# RevB.net
KiCad netlist of a schematic drawn in EAGLE
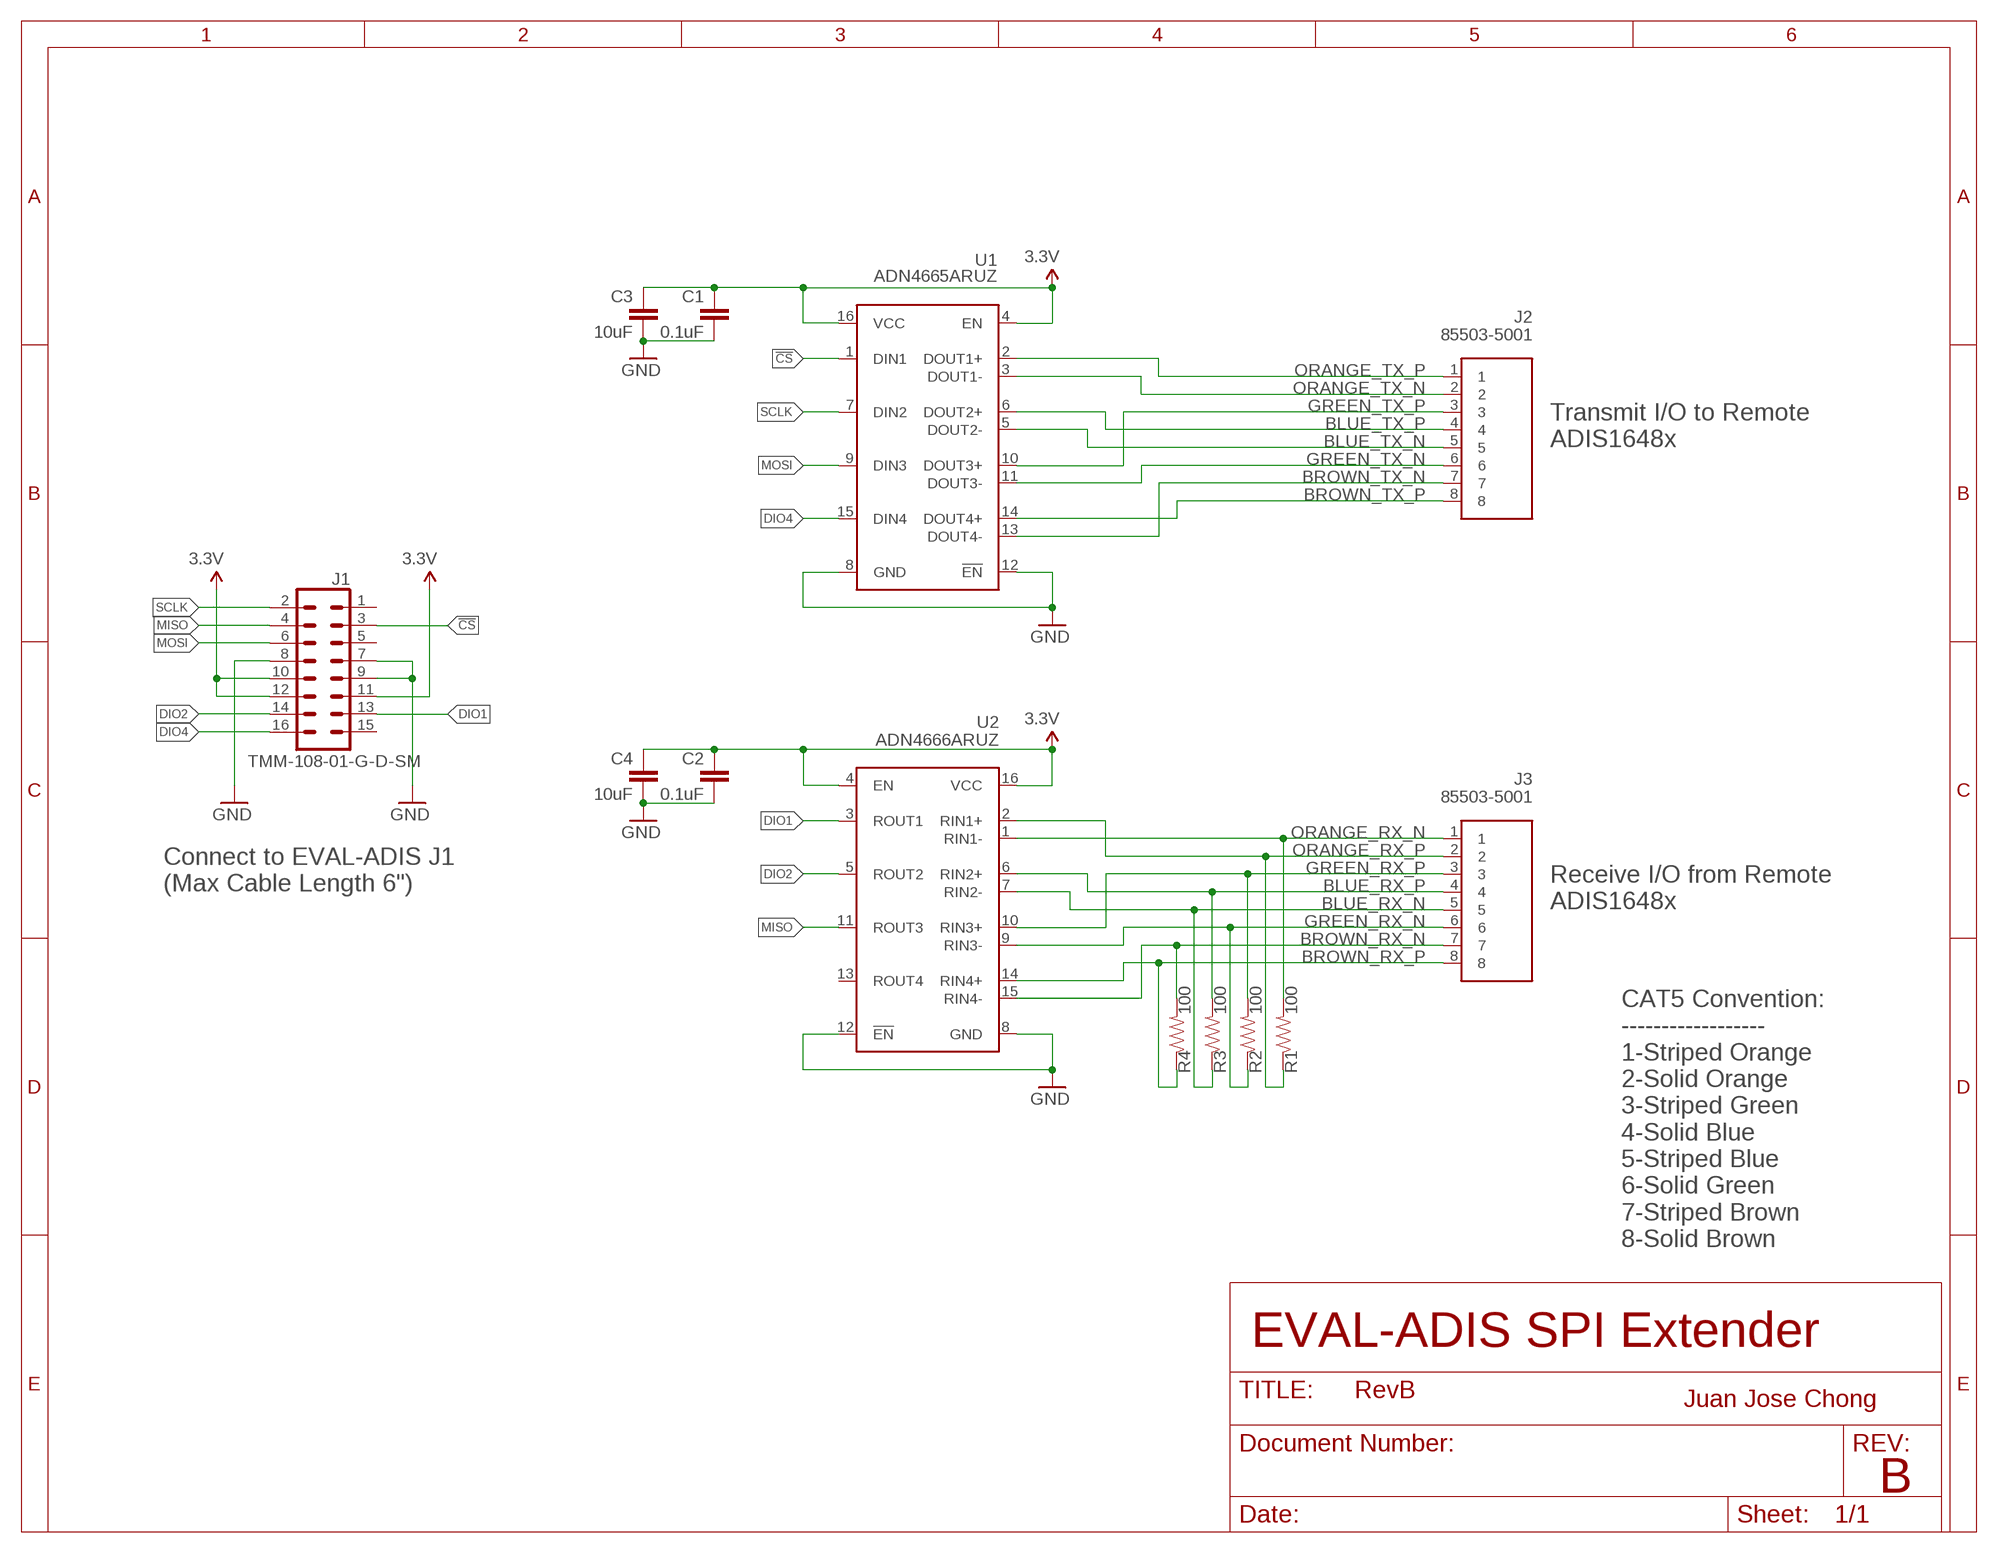
[diagram p0: schematic, sheet 1]

(export (version "E")
  (design (tool "Eeschema 10.0.6"))
  (components
    (comp (ref "C1")
      (value "0.1uF")
      (footprint "eagle-import:0805")
      (fields (field (name "PARTNO") "CL10B104KB8NNNC"))
      (libsource (lib "eagle-import") (part "CAP0805"))
    )
    (comp (ref "C2")
      (value "0.1uF")
      (footprint "eagle-import:0805")
      (fields (field (name "PARTNO") "CL10B104KB8NNNC"))
      (libsource (lib "eagle-import") (part "CAP0805"))
    )
    (comp (ref "C3")
      (value "10uF")
      (footprint "eagle-import:1206")
      (fields (field (name "PARTNO") "F931C106MAA"))
      (libsource (lib "eagle-import") (part "CAP1206"))
    )
    (comp (ref "C4")
      (value "10uF")
      (footprint "eagle-import:1206")
      (fields (field (name "PARTNO") "F931C106MAA"))
      (libsource (lib "eagle-import") (part "CAP1206"))
    )
    (comp (ref "J1")
      (value "TMM-108-01-G-D-SM")
      (footprint "eagle-import:TMM-108-XX-X-D")
      (libsource (lib "eagle-import") (part "TMM-108-XX-X-D"))
    )
    (comp (ref "J2")
      (value "85503-5001")
      (footprint "eagle-import:85503-5001")
      (fields (field (name "PARTNO") "855035001"))
      (libsource (lib "eagle-import") (part "85503-5001"))
    )
    (comp (ref "J3")
      (value "85503-5001")
      (footprint "eagle-import:85503-5001")
      (fields (field (name "PARTNO") "855035001"))
      (libsource (lib "eagle-import") (part "85503-5001"))
    )
    (comp (ref "R1")
      (value "100")
      (footprint "eagle-import:0603-RES")
      (fields (field (name "PARTNO") "ERJ-3EKF1000V"))
      (libsource (lib "eagle-import") (part "RESISTOR0603-RES"))
    )
    (comp (ref "R2")
      (value "100")
      (footprint "eagle-import:0603-RES")
      (fields (field (name "PARTNO") "ERJ-3EKF1000V"))
      (libsource (lib "eagle-import") (part "RESISTOR0603-RES"))
    )
    (comp (ref "R3")
      (value "100")
      (footprint "eagle-import:0603-RES")
      (fields (field (name "PARTNO") "ERJ-3EKF1000V"))
      (libsource (lib "eagle-import") (part "RESISTOR0603-RES"))
    )
    (comp (ref "R4")
      (value "100")
      (footprint "eagle-import:0603-RES")
      (fields (field (name "PARTNO") "ERJ-3EKF1000V"))
      (libsource (lib "eagle-import") (part "RESISTOR0603-RES"))
    )
    (comp (ref "U1")
      (value "ADN4665ARUZ")
      (footprint "eagle-import:TSSOP-16")
      (libsource (lib "eagle-import") (part "ADN4665ARUZ"))
    )
    (comp (ref "U2")
      (value "ADN4666ARUZ")
      (footprint "eagle-import:TSSOP-16")
      (libsource (lib "eagle-import") (part "ADN4666ARUZ"))
    )
  )
  (nets
    (net (code "1") (name "/BLUE_RX_N") (class "Default")
      (node (ref "J3") (pin "5") (pinfunction "5_5") (pintype "bidirectional"))
      (node (ref "R3") (pin "1") (pinfunction "1_1") (pintype "passive"))
      (node (ref "U2") (pin "7") (pinfunction "RIN2-_7") (pintype "bidirectional"))
    )
    (net (code "2") (name "/BLUE_RX_P") (class "Default")
      (node (ref "J3") (pin "4") (pinfunction "4_4") (pintype "bidirectional"))
      (node (ref "R3") (pin "2") (pinfunction "2_2") (pintype "passive"))
      (node (ref "U2") (pin "6") (pinfunction "RIN2+_6") (pintype "bidirectional"))
    )
    (net (code "3") (name "/BLUE_TX_N") (class "Default")
      (node (ref "J2") (pin "5") (pinfunction "5_5") (pintype "bidirectional"))
      (node (ref "U1") (pin "5") (pinfunction "DOUT2-_5") (pintype "bidirectional"))
    )
    (net (code "4") (name "/BLUE_TX_P") (class "Default")
      (node (ref "J2") (pin "4") (pinfunction "4_4") (pintype "bidirectional"))
      (node (ref "U1") (pin "6") (pinfunction "DOUT2+_6") (pintype "bidirectional"))
    )
    (net (code "5") (name "/BROWN_RX_N") (class "Default")
      (node (ref "J3") (pin "7") (pinfunction "7_7") (pintype "bidirectional"))
      (node (ref "R4") (pin "2") (pinfunction "2_2") (pintype "passive"))
      (node (ref "U2") (pin "15") (pinfunction "RIN4-_15") (pintype "bidirectional"))
    )
    (net (code "6") (name "/BROWN_RX_P") (class "Default")
      (node (ref "J3") (pin "8") (pinfunction "8_8") (pintype "bidirectional"))
      (node (ref "R4") (pin "1") (pinfunction "1_1") (pintype "passive"))
      (node (ref "U2") (pin "14") (pinfunction "RIN4+_14") (pintype "bidirectional"))
    )
    (net (code "7") (name "/BROWN_TX_N") (class "Default")
      (node (ref "J2") (pin "7") (pinfunction "7_7") (pintype "bidirectional"))
      (node (ref "U1") (pin "13") (pinfunction "DOUT4-_13") (pintype "bidirectional"))
    )
    (net (code "8") (name "/BROWN_TX_P") (class "Default")
      (node (ref "J2") (pin "8") (pinfunction "8_8") (pintype "bidirectional"))
      (node (ref "U1") (pin "14") (pinfunction "DOUT4+_14") (pintype "bidirectional"))
    )
    (net (code "9") (name "/GREEN_RX_N") (class "Default")
      (node (ref "J3") (pin "6") (pinfunction "6_6") (pintype "bidirectional"))
      (node (ref "R2") (pin "1") (pinfunction "1_1") (pintype "passive"))
      (node (ref "U2") (pin "9") (pinfunction "RIN3-_9") (pintype "bidirectional"))
    )
    (net (code "10") (name "/GREEN_RX_P") (class "Default")
      (node (ref "J3") (pin "3") (pinfunction "3_3") (pintype "bidirectional"))
      (node (ref "R2") (pin "2") (pinfunction "2_2") (pintype "passive"))
      (node (ref "U2") (pin "10") (pinfunction "RIN3+_10") (pintype "bidirectional"))
    )
    (net (code "11") (name "/GREEN_TX_N") (class "Default")
      (node (ref "J2") (pin "6") (pinfunction "6_6") (pintype "bidirectional"))
      (node (ref "U1") (pin "11") (pinfunction "DOUT3-_11") (pintype "bidirectional"))
    )
    (net (code "12") (name "/GREEN_TX_P") (class "Default")
      (node (ref "J2") (pin "3") (pinfunction "3_3") (pintype "bidirectional"))
      (node (ref "U1") (pin "10") (pinfunction "DOUT3+_10") (pintype "bidirectional"))
    )
    (net (code "13") (name "/ORANGE_RX_N") (class "Default")
      (node (ref "J3") (pin "1") (pinfunction "1_1") (pintype "bidirectional"))
      (node (ref "R1") (pin "2") (pinfunction "2_2") (pintype "passive"))
      (node (ref "U2") (pin "1") (pinfunction "RIN1-_1") (pintype "bidirectional"))
    )
    (net (code "14") (name "/ORANGE_RX_P") (class "Default")
      (node (ref "J3") (pin "2") (pinfunction "2_2") (pintype "bidirectional"))
      (node (ref "R1") (pin "1") (pinfunction "1_1") (pintype "passive"))
      (node (ref "U2") (pin "2") (pinfunction "RIN1+_2") (pintype "bidirectional"))
    )
    (net (code "15") (name "/ORANGE_TX_N") (class "Default")
      (node (ref "J2") (pin "2") (pinfunction "2_2") (pintype "bidirectional"))
      (node (ref "U1") (pin "3") (pinfunction "DOUT1-_3") (pintype "bidirectional"))
    )
    (net (code "16") (name "/ORANGE_TX_P") (class "Default")
      (node (ref "J2") (pin "1") (pinfunction "1_1") (pintype "bidirectional"))
      (node (ref "U1") (pin "2") (pinfunction "DOUT1+_2") (pintype "bidirectional"))
    )
    (net (code "17") (name "/~{CS}") (class "Default")
      (node (ref "J1") (pin "3") (pinfunction "3_3") (pintype "passive"))
      (node (ref "U1") (pin "1") (pinfunction "DIN1_1") (pintype "bidirectional"))
    )
    (net (code "18") (name "3.3V") (class "Default")
      (node (ref "C1") (pin "1") (pinfunction "1_1") (pintype "passive"))
      (node (ref "C2") (pin "1") (pinfunction "1_1") (pintype "passive"))
      (node (ref "C3") (pin "1") (pinfunction "1_1") (pintype "passive"))
      (node (ref "C4") (pin "1") (pinfunction "1_1") (pintype "passive"))
      (node (ref "J1") (pin "10") (pinfunction "10_10") (pintype "passive"))
      (node (ref "J1") (pin "11") (pinfunction "11_11") (pintype "passive"))
      (node (ref "J1") (pin "12") (pinfunction "12_12") (pintype "passive"))
      (node (ref "U1") (pin "16") (pinfunction "VCC_16") (pintype "bidirectional"))
      (node (ref "U1") (pin "4") (pinfunction "EN_4") (pintype "bidirectional"))
      (node (ref "U2") (pin "16") (pinfunction "VCC_16") (pintype "bidirectional"))
      (node (ref "U2") (pin "4") (pinfunction "EN_4") (pintype "bidirectional"))
    )
    (net (code "19") (name "DIO1") (class "Default")
      (node (ref "J1") (pin "13") (pinfunction "13_13") (pintype "passive"))
      (node (ref "U2") (pin "3") (pinfunction "ROUT1_3") (pintype "bidirectional"))
    )
    (net (code "20") (name "DIO2") (class "Default")
      (node (ref "J1") (pin "14") (pinfunction "14_14") (pintype "passive"))
      (node (ref "U2") (pin "5") (pinfunction "ROUT2_5") (pintype "bidirectional"))
    )
    (net (code "21") (name "DIO4") (class "Default")
      (node (ref "J1") (pin "16") (pinfunction "16_16") (pintype "passive"))
      (node (ref "U1") (pin "15") (pinfunction "DIN4_15") (pintype "bidirectional"))
    )
    (net (code "22") (name "GND") (class "Default")
      (node (ref "C1") (pin "2") (pinfunction "2_2") (pintype "passive"))
      (node (ref "C2") (pin "2") (pinfunction "2_2") (pintype "passive"))
      (node (ref "C3") (pin "2") (pinfunction "2_2") (pintype "passive"))
      (node (ref "C4") (pin "2") (pinfunction "2_2") (pintype "passive"))
      (node (ref "J1") (pin "7") (pinfunction "7_7") (pintype "passive"))
      (node (ref "J1") (pin "8") (pinfunction "8_8") (pintype "passive"))
      (node (ref "J1") (pin "9") (pinfunction "9_9") (pintype "passive"))
      (node (ref "U1") (pin "12") (pinfunction "~{EN}_12") (pintype "bidirectional"))
      (node (ref "U1") (pin "8") (pinfunction "GND_8") (pintype "bidirectional"))
      (node (ref "U2") (pin "12") (pinfunction "~{EN}_12") (pintype "bidirectional"))
      (node (ref "U2") (pin "8") (pinfunction "GND_8") (pintype "bidirectional"))
    )
    (net (code "23") (name "MISO") (class "Default")
      (node (ref "J1") (pin "4") (pinfunction "4_4") (pintype "passive"))
      (node (ref "U2") (pin "11") (pinfunction "ROUT3_11") (pintype "bidirectional"))
    )
    (net (code "24") (name "MOSI") (class "Default")
      (node (ref "J1") (pin "6") (pinfunction "6_6") (pintype "passive"))
      (node (ref "U1") (pin "9") (pinfunction "DIN3_9") (pintype "bidirectional"))
    )
    (net (code "25") (name "SCLK") (class "Default")
      (node (ref "J1") (pin "2") (pinfunction "2_2") (pintype "passive"))
      (node (ref "U1") (pin "7") (pinfunction "DIN2_7") (pintype "bidirectional"))
    )
    (net (code "26") (name "unconnected-(J1-Pad1)") (class "Default")
      (node (ref "J1") (pin "1") (pinfunction "1_1") (pintype "passive"))
    )
    (net (code "27") (name "unconnected-(J1-Pad5)") (class "Default")
      (node (ref "J1") (pin "5") (pinfunction "5_5") (pintype "passive"))
    )
    (net (code "28") (name "unconnected-(J1-Pad15)") (class "Default")
      (node (ref "J1") (pin "15") (pinfunction "15_15") (pintype "passive"))
    )
    (net (code "29") (name "unconnected-(U2-ROUT4-Pad13)") (class "Default")
      (node (ref "U2") (pin "13") (pinfunction "ROUT4_13") (pintype "bidirectional"))
    )
  )
)
